# os21_smt.net
KiCad netlist of a schematic drawn in EAGLE
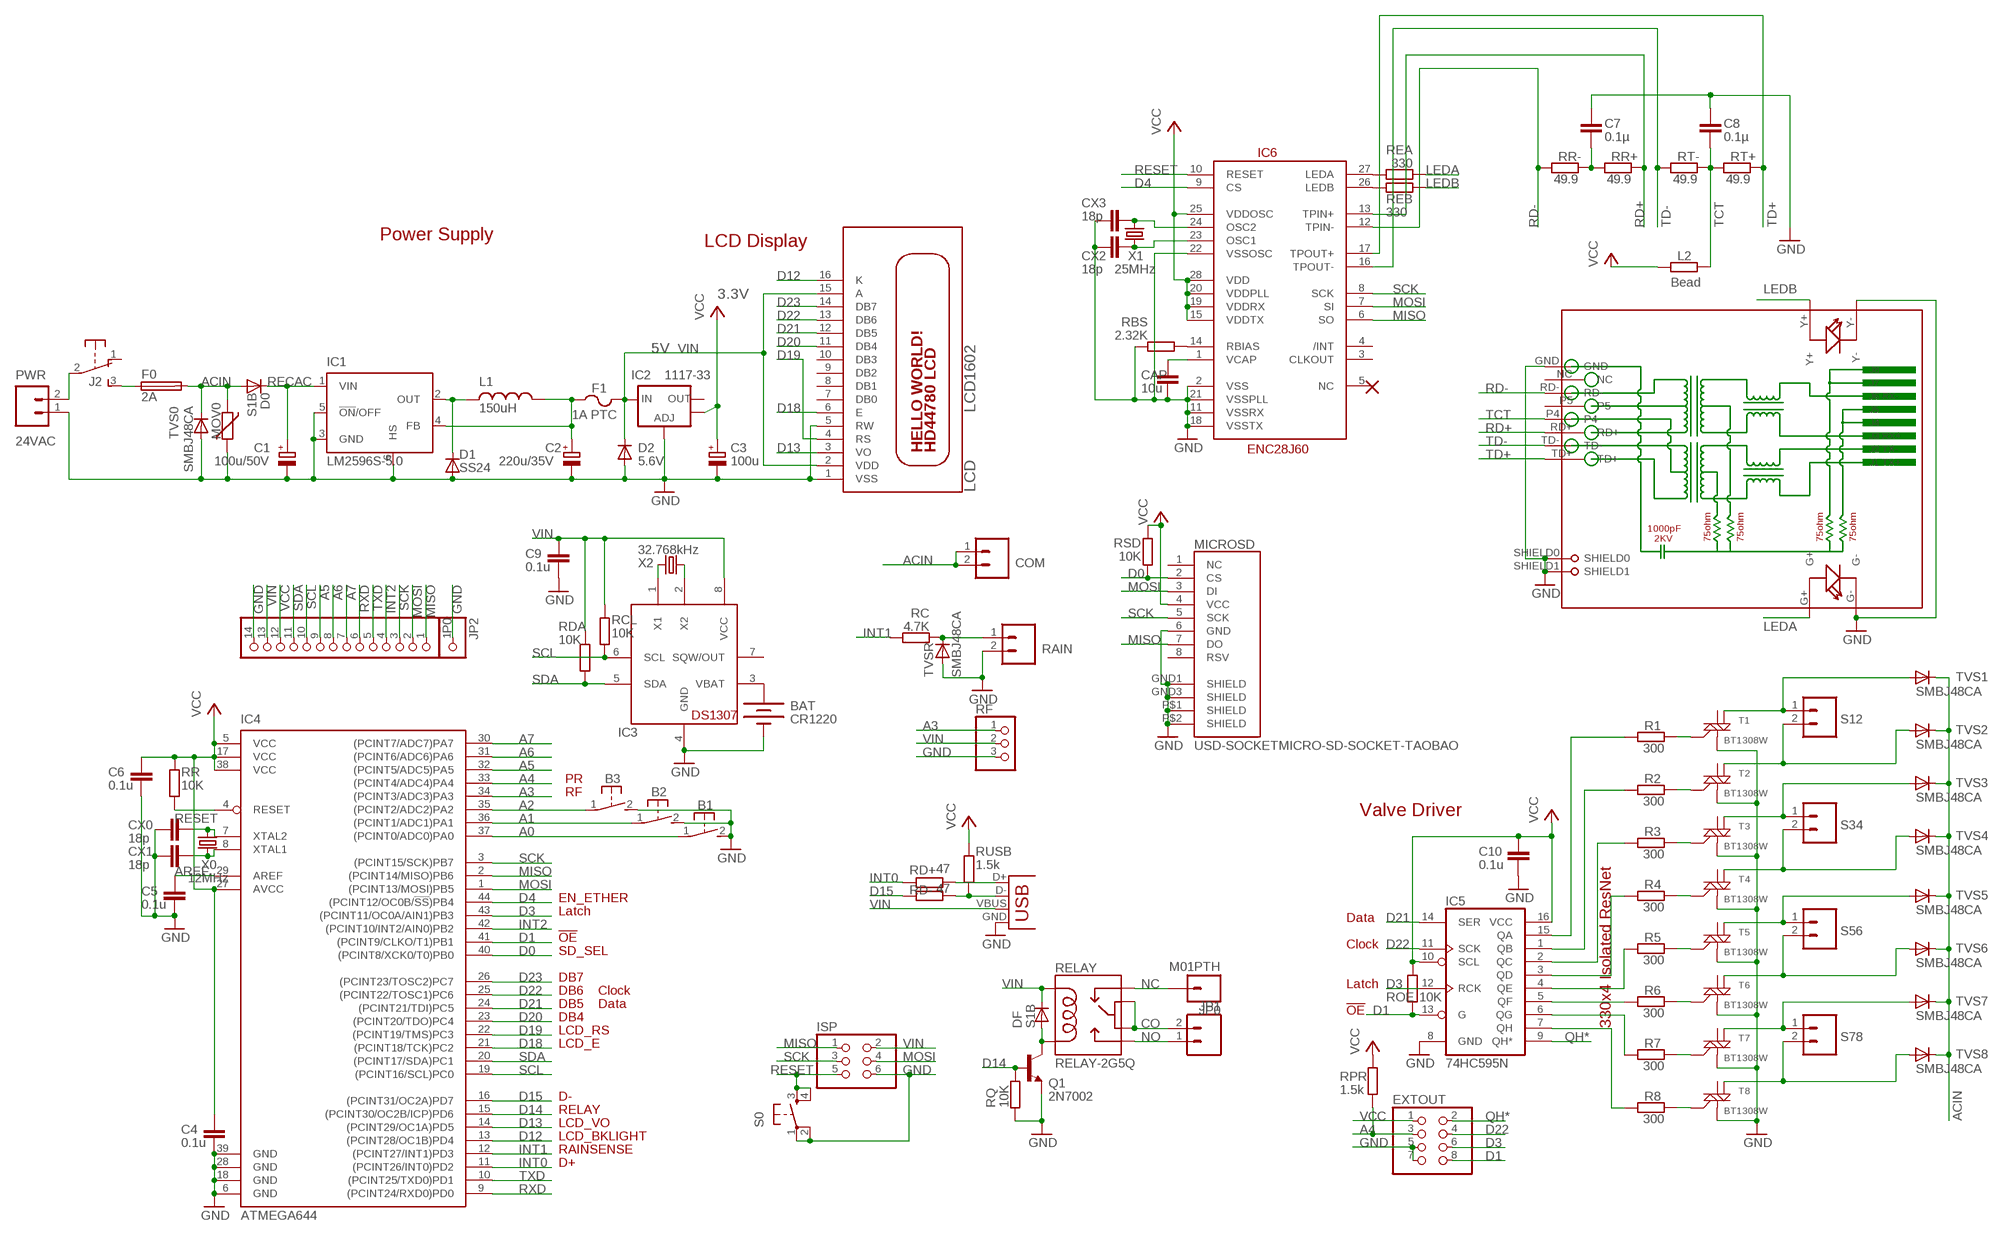
[diagram p0: schematic, sheet 1]

(export (version "E")
  (design (tool "Eeschema 10.0.6"))
  (components
    (comp (ref "B1")
      (value "31-XX")
      (footprint "eagle-import:B3F-31XX")
      (libsource (lib "eagle-import") (part "31-XX"))
    )
    (comp (ref "B2")
      (value "31-XX")
      (footprint "eagle-import:B3F-31XX")
      (libsource (lib "eagle-import") (part "31-XX"))
    )
    (comp (ref "B3")
      (value "31-XX")
      (footprint "eagle-import:B3F-31XX")
      (libsource (lib "eagle-import") (part "31-XX"))
    )
    (comp (ref "BAT")
      (value "CR1220")
      (footprint "eagle-import:BATTCON_12MM_SMT")
      (libsource (lib "eagle-import") (part "BATTERYBATTERY_12MM_SMT"))
    )
    (comp (ref "C1")
      (value "100u/50V")
      (footprint "eagle-import:E3,5-8")
      (libsource (lib "eagle-import") (part "CPOL-EUE3.5-8"))
    )
    (comp (ref "C2")
      (value "220u/35V")
      (footprint "eagle-import:E3,5-8")
      (libsource (lib "eagle-import") (part "CPOL-EUE3.5-8"))
    )
    (comp (ref "C3")
      (value "100u")
      (footprint "eagle-import:PANASONIC_D")
      (libsource (lib "eagle-import") (part "CPOL-EUD"))
    )
    (comp (ref "C4")
      (value "0.1u")
      (footprint "eagle-import:C0805")
      (libsource (lib "eagle-import") (part "C-EUC0805"))
    )
    (comp (ref "C5")
      (value "0.1u")
      (footprint "eagle-import:C0805")
      (libsource (lib "eagle-import") (part "C-EUC0805"))
    )
    (comp (ref "C6")
      (value "0.1u")
      (footprint "eagle-import:C0805")
      (libsource (lib "eagle-import") (part "C-EUC0805"))
    )
    (comp (ref "C7")
      (value "0.1µ")
      (footprint "eagle-import:C0805")
      (libsource (lib "eagle-import") (part "resistor_C-EUC0805"))
    )
    (comp (ref "C8")
      (value "0.1µ")
      (footprint "eagle-import:C0805")
      (libsource (lib "eagle-import") (part "resistor_C-EUC0805"))
    )
    (comp (ref "C9")
      (value "0.1u")
      (footprint "eagle-import:C0805")
      (libsource (lib "eagle-import") (part "C-EUC0805"))
    )
    (comp (ref "C10")
      (value "0.1u")
      (footprint "eagle-import:C0805")
      (libsource (lib "eagle-import") (part "C-EUC0805"))
    )
    (comp (ref "CAP")
      (value "10u")
      (footprint "eagle-import:C0805")
      (libsource (lib "eagle-import") (part "resistor_C-EUC0805"))
    )
    (comp (ref "COM")
      (value "M025MM-X")
      (footprint "eagle-import:SCREWTERMINAL-5MM-2-X")
      (libsource (lib "eagle-import") (part "M025MM-X"))
    )
    (comp (ref "CX0")
      (value "18p")
      (footprint "eagle-import:C0805")
      (libsource (lib "eagle-import") (part "resistor_C-EUC0805"))
    )
    (comp (ref "CX1")
      (value "18p")
      (footprint "eagle-import:C0805")
      (libsource (lib "eagle-import") (part "resistor_C-EUC0805"))
    )
    (comp (ref "CX2")
      (value "18p")
      (footprint "eagle-import:C0805")
      (libsource (lib "eagle-import") (part "resistor_C-EUC0805"))
    )
    (comp (ref "CX3")
      (value "18p")
      (footprint "eagle-import:C0805")
      (libsource (lib "eagle-import") (part "resistor_C-EUC0805"))
    )
    (comp (ref "D0")
      (value "S1B")
      (footprint "eagle-import:DO-214AC")
      (libsource (lib "eagle-import") (part "DIODE-DO-214AC"))
    )
    (comp (ref "D1")
      (value "SS24")
      (footprint "eagle-import:SMB")
      (libsource (lib "eagle-import") (part "DIODE-SMB"))
    )
    (comp (ref "D2")
      (value "5.6V")
      (footprint "eagle-import:MINIMELF")
      (libsource (lib "eagle-import") (part "DIODE-MINIMELF"))
    )
    (comp (ref "DF")
      (value "S1B")
      (footprint "eagle-import:DO-214AC")
      (libsource (lib "eagle-import") (part "DIODE-DO-214AC"))
    )
    (comp (ref "EXTOUT")
      (value "PINHD-2X4")
      (footprint "eagle-import:2X04")
      (libsource (lib "eagle-import") (part "PINHD-2X4"))
    )
    (comp (ref "F0")
      (value "2A")
      (footprint "eagle-import:SHK20L")
      (libsource (lib "eagle-import") (part "FUSESHK20L"))
    )
    (comp (ref "F1")
      (value "1A PTC")
      (footprint "eagle-import:1812")
      (libsource (lib "eagle-import") (part "PTCFUSE-1812"))
    )
    (comp (ref "IC1")
      (value "LM2596S-5.0")
      (footprint "eagle-import:TO263-5")
      (fields (field (name "MF") "NATIONAL SEMICONDUCTOR") (field (name "MPN") "LM2596S-ADJ/NOPB"))
      (libsource (lib "eagle-import") (part "LM2596S"))
    )
    (comp (ref "IC2")
      (value "1117-33")
      (footprint "eagle-import:SOT223")
      (libsource (lib "eagle-import") (part "V_REG_LM1117SOT223"))
    )
    (comp (ref "IC3")
      (value "DS1307")
      (footprint "eagle-import:SO08")
      (libsource (lib "eagle-import") (part "DS1307SOIC"))
    )
    (comp (ref "IC4")
      (value "ATMEGA644")
      (footprint "eagle-import:TQFP44")
      (fields (field (name "MPN") "ATMEGA644PV-10AU"))
      (libsource (lib "eagle-import") (part "ATMEGA644A"))
    )
    (comp (ref "IC5")
      (value "74HC595N")
      (footprint "eagle-import:SO16")
      (libsource (lib "eagle-import") (part "74595DLS"))
    )
    (comp (ref "IC6")
      (value "ENC28J60")
      (footprint "eagle-import:SOIC28WLONG")
      (libsource (lib "eagle-import") (part "ENC28J60SO28LONG"))
    )
    (comp (ref "ISP")
      (value "PINHD-2X3")
      (footprint "eagle-import:2X03")
      (libsource (lib "eagle-import") (part "PINHD-2X3"))
    )
    (comp (ref "J2")
      (value "EG1206")
      (footprint "eagle-import:EG1206")
      (libsource (lib "eagle-import") (part "EG1206"))
    )
    (comp (ref "JP0")
      (value "M01PTH")
      (footprint "eagle-import:1X01")
      (libsource (lib "eagle-import") (part "M01PTH"))
    )
    (comp (ref "JP1")
      (value "M025MM-X")
      (footprint "eagle-import:SCREWTERMINAL-5MM-2-X")
      (libsource (lib "eagle-import") (part "M025MM-X"))
    )
    (comp (ref "JP2")
      (value "PINHD-1X1CB")
      (footprint "eagle-import:1X01-CLEANBIG")
      (libsource (lib "eagle-import") (part "PINHD-1X1CB"))
    )
    (comp (ref "L1")
      (value "150uH")
      (footprint "eagle-import:CDRH125")
      (libsource (lib "eagle-import") (part "INDUCTORPWR"))
    )
    (comp (ref "L2")
      (value "Bead")
      (footprint "eagle-import:R0805")
      (libsource (lib "eagle-import") (part "R-EU_R0805"))
    )
    (comp (ref "LCD")
      (value "LCD1602")
      (footprint "eagle-import:LCD1602A")
      (libsource (lib "eagle-import") (part "HD44780LCDNOHOLE"))
    )
    (comp (ref "MICROSD")
      (value "USD-SOCKETMICRO-SD-SOCKET-TAOBAO")
      (footprint "eagle-import:MICRO-SD-SOCKET-TAOBAO")
      (libsource (lib "eagle-import") (part "USD-SOCKETMICRO-SD-SOCKET-TAOBAO"))
    )
    (comp (ref "MOV0")
      (value "MOV")
      (footprint "eagle-import:R-5")
      (libsource (lib "eagle-import") (part "VARISTOR-5"))
    )
    (comp (ref "P0")
      (value "PINHD-1X14-CB")
      (footprint "eagle-import:1X14-CB")
      (libsource (lib "eagle-import") (part "PINHD-1X14-CB"))
    )
    (comp (ref "PWR")
      (value "24VAC")
      (footprint "eagle-import:SCREWTERMINAL-4MM-2-X")
      (libsource (lib "eagle-import") (part "M024MM-X"))
    )
    (comp (ref "Q1")
      (value "2N7002")
      (footprint "eagle-import:SOT23-3")
      (libsource (lib "eagle-import") (part "TRANSISTOR_NPNSOT23-3"))
    )
    (comp (ref "R1")
      (value "300")
      (footprint "eagle-import:R0805")
      (libsource (lib "eagle-import") (part "R-EU_R0805"))
    )
    (comp (ref "R2")
      (value "300")
      (footprint "eagle-import:R0805")
      (libsource (lib "eagle-import") (part "R-EU_R0805"))
    )
    (comp (ref "R3")
      (value "300")
      (footprint "eagle-import:R0805")
      (libsource (lib "eagle-import") (part "R-EU_R0805"))
    )
    (comp (ref "R4")
      (value "300")
      (footprint "eagle-import:R0805")
      (libsource (lib "eagle-import") (part "R-EU_R0805"))
    )
    (comp (ref "R5")
      (value "300")
      (footprint "eagle-import:R0805")
      (libsource (lib "eagle-import") (part "R-EU_R0805"))
    )
    (comp (ref "R6")
      (value "300")
      (footprint "eagle-import:R0805")
      (libsource (lib "eagle-import") (part "R-EU_R0805"))
    )
    (comp (ref "R7")
      (value "300")
      (footprint "eagle-import:R0805")
      (libsource (lib "eagle-import") (part "R-EU_R0805"))
    )
    (comp (ref "R8")
      (value "300")
      (footprint "eagle-import:R0805")
      (libsource (lib "eagle-import") (part "R-EU_R0805"))
    )
    (comp (ref "RAIN")
      (value "M025MM-X")
      (footprint "eagle-import:SCREWTERMINAL-5MM-2-X")
      (libsource (lib "eagle-import") (part "M025MM-X"))
    )
    (comp (ref "RBS")
      (value "2.32K")
      (footprint "eagle-import:R0805")
      (libsource (lib "eagle-import") (part "R-EU_R0805"))
    )
    (comp (ref "RC")
      (value "4.7K")
      (footprint "eagle-import:R0805")
      (libsource (lib "eagle-import") (part "R-EU_R0805"))
    )
    (comp (ref "RCL")
      (value "10K")
      (footprint "eagle-import:R0805")
      (libsource (lib "eagle-import") (part "R-EU_R0805"))
    )
    (comp (ref "RD+")
      (value "47")
      (footprint "eagle-import:R0805")
      (libsource (lib "eagle-import") (part "R-EU_R0805"))
    )
    (comp (ref "RD-")
      (value "47")
      (footprint "eagle-import:R0805")
      (libsource (lib "eagle-import") (part "R-EU_R0805"))
    )
    (comp (ref "RDA")
      (value "10K")
      (footprint "eagle-import:R0805")
      (libsource (lib "eagle-import") (part "R-EU_R0805"))
    )
    (comp (ref "REA")
      (value "330")
      (footprint "eagle-import:R0805")
      (libsource (lib "eagle-import") (part "R-EU_R0805"))
    )
    (comp (ref "REB")
      (value "330")
      (footprint "eagle-import:R0805")
      (libsource (lib "eagle-import") (part "R-EU_R0805"))
    )
    (comp (ref "RELAY")
      (value "RELAY-2G5Q")
      (footprint "eagle-import:RELAY-G5V")
      (libsource (lib "eagle-import") (part "RELAY-2G5Q"))
    )
    (comp (ref "RF")
      (value "PINHD-1X3")
      (footprint "eagle-import:1X03")
      (libsource (lib "eagle-import") (part "PINHD-1X3"))
    )
    (comp (ref "RJ45")
      (value "HR911105A")
      (footprint "eagle-import:HR911105A")
      (libsource (lib "eagle-import") (part "HR911105A"))
    )
    (comp (ref "ROE")
      (value "10K")
      (footprint "eagle-import:R0805")
      (libsource (lib "eagle-import") (part "R-EU_R0805"))
    )
    (comp (ref "RPR")
      (value "1.5k")
      (footprint "eagle-import:R0805")
      (libsource (lib "eagle-import") (part "R-EU_R0805"))
    )
    (comp (ref "RQ")
      (value "10K")
      (footprint "eagle-import:R0805")
      (libsource (lib "eagle-import") (part "R-EU_R0805"))
    )
    (comp (ref "RR")
      (value "10K")
      (footprint "eagle-import:R0805")
      (libsource (lib "eagle-import") (part "R-EU_R0805"))
    )
    (comp (ref "RR+")
      (value "49.9")
      (footprint "eagle-import:R0805")
      (libsource (lib "eagle-import") (part "R-EU_R0805"))
    )
    (comp (ref "RR-")
      (value "49.9")
      (footprint "eagle-import:R0805")
      (libsource (lib "eagle-import") (part "R-EU_R0805"))
    )
    (comp (ref "RSD")
      (value "10K")
      (footprint "eagle-import:R0805")
      (libsource (lib "eagle-import") (part "R-EU_R0805"))
    )
    (comp (ref "RT+")
      (value "49.9")
      (footprint "eagle-import:R0805")
      (libsource (lib "eagle-import") (part "R-EU_R0805"))
    )
    (comp (ref "RT-")
      (value "49.9")
      (footprint "eagle-import:R0805")
      (libsource (lib "eagle-import") (part "R-EU_R0805"))
    )
    (comp (ref "RUSB")
      (value "1.5k")
      (footprint "eagle-import:R0805")
      (libsource (lib "eagle-import") (part "R-EU_R0805"))
    )
    (comp (ref "S0")
      (value "TAC_SWITCHSMD")
      (footprint "eagle-import:TACTILE_SWITCH_SMD")
      (libsource (lib "eagle-import") (part "TAC_SWITCHSMD"))
    )
    (comp (ref "S12")
      (value "M025MM-X")
      (footprint "eagle-import:SCREWTERMINAL-5MM-2-X")
      (libsource (lib "eagle-import") (part "M025MM-X"))
    )
    (comp (ref "S34")
      (value "M025MM-X")
      (footprint "eagle-import:SCREWTERMINAL-5MM-2-X")
      (libsource (lib "eagle-import") (part "M025MM-X"))
    )
    (comp (ref "S56")
      (value "M025MM-X")
      (footprint "eagle-import:SCREWTERMINAL-5MM-2-X")
      (libsource (lib "eagle-import") (part "M025MM-X"))
    )
    (comp (ref "S78")
      (value "M025MM-X")
      (footprint "eagle-import:SCREWTERMINAL-5MM-2-X")
      (libsource (lib "eagle-import") (part "M025MM-X"))
    )
    (comp (ref "T1")
      (value "BT1308W")
      (footprint "eagle-import:SOT223")
      (libsource (lib "eagle-import") (part "MAC97SOT223"))
    )
    (comp (ref "T2")
      (value "BT1308W")
      (footprint "eagle-import:SOT223")
      (libsource (lib "eagle-import") (part "MAC97SOT223"))
    )
    (comp (ref "T3")
      (value "BT1308W")
      (footprint "eagle-import:SOT223")
      (libsource (lib "eagle-import") (part "MAC97SOT223"))
    )
    (comp (ref "T4")
      (value "BT1308W")
      (footprint "eagle-import:SOT223")
      (libsource (lib "eagle-import") (part "MAC97SOT223"))
    )
    (comp (ref "T5")
      (value "BT1308W")
      (footprint "eagle-import:SOT223")
      (libsource (lib "eagle-import") (part "MAC97SOT223"))
    )
    (comp (ref "T6")
      (value "BT1308W")
      (footprint "eagle-import:SOT223")
      (libsource (lib "eagle-import") (part "MAC97SOT223"))
    )
    (comp (ref "T7")
      (value "BT1308W")
      (footprint "eagle-import:SOT223")
      (libsource (lib "eagle-import") (part "MAC97SOT223"))
    )
    (comp (ref "T8")
      (value "BT1308W")
      (footprint "eagle-import:SOT223")
      (libsource (lib "eagle-import") (part "MAC97SOT223"))
    )
    (comp (ref "TVS0")
      (value "SMBJ48CA")
      (footprint "eagle-import:SMB")
      (libsource (lib "eagle-import") (part "DIODE-SMB"))
    )
    (comp (ref "TVS1")
      (value "SMBJ48CA")
      (footprint "eagle-import:SMB")
      (libsource (lib "eagle-import") (part "DIODE-SMB"))
    )
    (comp (ref "TVS2")
      (value "SMBJ48CA")
      (footprint "eagle-import:SMB")
      (libsource (lib "eagle-import") (part "DIODE-SMB"))
    )
    (comp (ref "TVS3")
      (value "SMBJ48CA")
      (footprint "eagle-import:SMB")
      (libsource (lib "eagle-import") (part "DIODE-SMB"))
    )
    (comp (ref "TVS4")
      (value "SMBJ48CA")
      (footprint "eagle-import:SMB")
      (libsource (lib "eagle-import") (part "DIODE-SMB"))
    )
    (comp (ref "TVS5")
      (value "SMBJ48CA")
      (footprint "eagle-import:SMB")
      (libsource (lib "eagle-import") (part "DIODE-SMB"))
    )
    (comp (ref "TVS6")
      (value "SMBJ48CA")
      (footprint "eagle-import:SMB")
      (libsource (lib "eagle-import") (part "DIODE-SMB"))
    )
    (comp (ref "TVS7")
      (value "SMBJ48CA")
      (footprint "eagle-import:SMB")
      (libsource (lib "eagle-import") (part "DIODE-SMB"))
    )
    (comp (ref "TVS8")
      (value "SMBJ48CA")
      (footprint "eagle-import:SMB")
      (libsource (lib "eagle-import") (part "DIODE-SMB"))
    )
    (comp (ref "TVSR")
      (value "SMBJ48CA")
      (footprint "eagle-import:SMB")
      (libsource (lib "eagle-import") (part "DIODE-SMB"))
    )
    (comp (ref "USB")
      (value "USBPTH")
      (footprint "eagle-import:USB-B-PTH")
      (libsource (lib "eagle-import") (part "USBPTH"))
    )
    (comp (ref "X0")
      (value "12MHz")
      (footprint "eagle-import:HC49U-V")
      (libsource (lib "eagle-import") (part "CRYSTALHC49UV"))
    )
    (comp (ref "X1")
      (value "25MHz")
      (footprint "eagle-import:HC49U-V")
      (libsource (lib "eagle-import") (part "CRYSTALHC49UV"))
    )
    (comp (ref "X2")
      (value "32.768kHz")
      (footprint "eagle-import:TC38H")
      (libsource (lib "eagle-import") (part "crystal_CRYSTALTC38H"))
    )
  )
  (nets
    (net (code "1") (name "/A0") (class "Default")
      (node (ref "B1") (pin "1") (pinfunction "P_1") (pintype "passive"))
      (node (ref "IC4") (pin "37") (pinfunction "(PCINT0/ADC0)PA0_37") (pintype "bidirectional"))
    )
    (net (code "2") (name "/A1") (class "Default")
      (node (ref "B2") (pin "1") (pinfunction "P_1") (pintype "passive"))
      (node (ref "IC4") (pin "36") (pinfunction "(PCINT1/ADC1)PA1_36") (pintype "bidirectional"))
    )
    (net (code "3") (name "/A2") (class "Default")
      (node (ref "B3") (pin "1") (pinfunction "P_1") (pintype "passive"))
      (node (ref "IC4") (pin "35") (pinfunction "(PCINT2/ADC2)PA2_35") (pintype "bidirectional"))
    )
    (net (code "4") (name "/A3") (class "Default")
      (node (ref "IC4") (pin "34") (pinfunction "(PCINT3/ADC3)PA3_34") (pintype "bidirectional"))
      (node (ref "RF") (pin "1") (pinfunction "1_1") (pintype "passive"))
    )
    (net (code "5") (name "/A4") (class "Default")
      (node (ref "EXTOUT") (pin "3") (pinfunction "3_3") (pintype "passive"))
      (node (ref "IC4") (pin "33") (pinfunction "(PCINT4/ADC4)PA4_33") (pintype "bidirectional"))
      (node (ref "RPR") (pin "1") (pinfunction "1_1") (pintype "passive"))
    )
    (net (code "6") (name "/A5") (class "Default")
      (node (ref "IC4") (pin "32") (pinfunction "(PCINT5/ADC5)PA5_32") (pintype "bidirectional"))
      (node (ref "P0") (pin "9") (pinfunction "9_9") (pintype "passive"))
    )
    (net (code "7") (name "/A6") (class "Default")
      (node (ref "IC4") (pin "31") (pinfunction "(PCINT6/ADC6)PA6_31") (pintype "bidirectional"))
      (node (ref "P0") (pin "8") (pinfunction "8_8") (pintype "passive"))
    )
    (net (code "8") (name "/A7") (class "Default")
      (node (ref "IC4") (pin "30") (pinfunction "(PCINT7/ADC7)PA7_30") (pintype "bidirectional"))
      (node (ref "P0") (pin "7") (pinfunction "7_7") (pintype "passive"))
    )
    (net (code "9") (name "/ACIN") (class "Default")
      (node (ref "COM") (pin "1") (pinfunction "1_1") (pintype "passive"))
      (node (ref "COM") (pin "2") (pinfunction "2_2") (pintype "passive"))
      (node (ref "D0") (pin "A") (pinfunction "A_A") (pintype "passive"))
      (node (ref "F0") (pin "2A") (pinfunction "2_2A") (pintype "passive"))
      (node (ref "MOV0") (pin "1") (pinfunction "1_1") (pintype "passive"))
      (node (ref "TVS0") (pin "C") (pinfunction "C_C") (pintype "passive"))
      (node (ref "TVS1") (pin "C") (pinfunction "C_C") (pintype "passive"))
      (node (ref "TVS2") (pin "C") (pinfunction "C_C") (pintype "passive"))
      (node (ref "TVS3") (pin "C") (pinfunction "C_C") (pintype "passive"))
      (node (ref "TVS4") (pin "C") (pinfunction "C_C") (pintype "passive"))
      (node (ref "TVS5") (pin "C") (pinfunction "C_C") (pintype "passive"))
      (node (ref "TVS6") (pin "C") (pinfunction "C_C") (pintype "passive"))
      (node (ref "TVS7") (pin "C") (pinfunction "C_C") (pintype "passive"))
      (node (ref "TVS8") (pin "C") (pinfunction "C_C") (pintype "passive"))
    )
    (net (code "10") (name "/AREF") (class "Default")
      (node (ref "C5") (pin "1") (pinfunction "1_1") (pintype "passive"))
      (node (ref "IC4") (pin "29") (pinfunction "AREF_29") (pintype "passive"))
    )
    (net (code "11") (name "/CO") (class "Default")
      (node (ref "JP1") (pin "2") (pinfunction "2_2") (pintype "passive"))
      (node (ref "RELAY") (pin "5") (pinfunction "5_5") (pintype "bidirectional"))
      (node (ref "RELAY") (pin "6") (pinfunction "6_6") (pintype "bidirectional"))
    )
    (net (code "12") (name "/D0") (class "Default")
      (node (ref "IC4") (pin "40") (pinfunction "(PCINT8/XCK0/T0)PB0_40") (pintype "bidirectional"))
      (node (ref "MICROSD") (pin "2") (pinfunction "CS_2") (pintype "bidirectional"))
      (node (ref "RSD") (pin "1") (pinfunction "1_1") (pintype "passive"))
    )
    (net (code "13") (name "/D1") (class "Default")
      (node (ref "EXTOUT") (pin "8") (pinfunction "8_8") (pintype "passive"))
      (node (ref "IC4") (pin "41") (pinfunction "(PCINT9/CLKO/T1)PB1_41") (pintype "bidirectional"))
      (node (ref "IC5") (pin "13") (pinfunction "G_13") (pintype "input"))
      (node (ref "ROE") (pin "1") (pinfunction "1_1") (pintype "passive"))
    )
    (net (code "14") (name "/D3") (class "Default")
      (node (ref "EXTOUT") (pin "6") (pinfunction "6_6") (pintype "passive"))
      (node (ref "IC4") (pin "43") (pinfunction "(PCINT11/OC0A/AIN1)PB3_43") (pintype "bidirectional"))
      (node (ref "IC5") (pin "12") (pinfunction "RCK_12") (pintype "input"))
    )
    (net (code "15") (name "/D4") (class "Default")
      (node (ref "IC4") (pin "44") (pinfunction "(PCINT12/OC0B/~{SS})PB4_44") (pintype "bidirectional"))
      (node (ref "IC6") (pin "9") (pinfunction "CS_9") (pintype "bidirectional"))
    )
    (net (code "16") (name "/D12") (class "Default")
      (node (ref "IC4") (pin "13") (pinfunction "(PCINT28/OC1B)PD4_13") (pintype "bidirectional"))
      (node (ref "LCD") (pin "16") (pinfunction "K_16") (pintype "input"))
    )
    (net (code "17") (name "/D13") (class "Default")
      (node (ref "IC4") (pin "14") (pinfunction "(PCINT29/OC1A)PD5_14") (pintype "bidirectional"))
      (node (ref "LCD") (pin "3") (pinfunction "VO_3") (pintype "input"))
    )
    (net (code "18") (name "/D14") (class "Default")
      (node (ref "IC4") (pin "15") (pinfunction "(PCINT30/OC2B/ICP)PD6_15") (pintype "bidirectional"))
      (node (ref "Q1") (pin "1") (pinfunction "B_1") (pintype "passive"))
      (node (ref "RQ") (pin "1") (pinfunction "1_1") (pintype "passive"))
    )
    (net (code "19") (name "/D15") (class "Default")
      (node (ref "IC4") (pin "16") (pinfunction "(PCINT31/OC2A)PD7_16") (pintype "bidirectional"))
      (node (ref "RD-") (pin "1") (pinfunction "1_1") (pintype "passive"))
    )
    (net (code "20") (name "/D18") (class "Default")
      (node (ref "IC4") (pin "21") (pinfunction "(PCINT18/TCK)PC2_21") (pintype "output"))
      (node (ref "LCD") (pin "6") (pinfunction "E_6") (pintype "input"))
    )
    (net (code "21") (name "/D19") (class "Default")
      (node (ref "IC4") (pin "22") (pinfunction "(PCINT19/TMS)PC3_22") (pintype "output"))
      (node (ref "LCD") (pin "4") (pinfunction "RS_4") (pintype "input"))
    )
    (net (code "22") (name "/D20") (class "Default")
      (node (ref "IC4") (pin "23") (pinfunction "(PCINT20/TDO)PC4_23") (pintype "output"))
      (node (ref "LCD") (pin "11") (pinfunction "DB4_11") (pintype "bidirectional"))
    )
    (net (code "23") (name "/D21") (class "Default")
      (node (ref "IC4") (pin "24") (pinfunction "(PCINT21/TDI)PC5_24") (pintype "output"))
      (node (ref "IC5") (pin "14") (pinfunction "SER_14") (pintype "input"))
      (node (ref "LCD") (pin "12") (pinfunction "DB5_12") (pintype "bidirectional"))
    )
    (net (code "24") (name "/D22") (class "Default")
      (node (ref "EXTOUT") (pin "4") (pinfunction "4_4") (pintype "passive"))
      (node (ref "IC4") (pin "25") (pinfunction "(PCINT22/TOSC1)PC6_25") (pintype "output"))
      (node (ref "IC5") (pin "11") (pinfunction "SCK_11") (pintype "input"))
      (node (ref "LCD") (pin "13") (pinfunction "DB6_13") (pintype "bidirectional"))
    )
    (net (code "25") (name "/D23") (class "Default")
      (node (ref "IC4") (pin "26") (pinfunction "(PCINT23/TOSC2)PC7_26") (pintype "output"))
      (node (ref "LCD") (pin "14") (pinfunction "DB7_14") (pintype "bidirectional"))
    )
    (net (code "26") (name "/INT0") (class "Default")
      (node (ref "IC4") (pin "11") (pinfunction "(PCINT26/INT0)PD2_11") (pintype "bidirectional"))
      (node (ref "RD+") (pin "1") (pinfunction "1_1") (pintype "passive"))
    )
    (net (code "27") (name "/INT1") (class "Default")
      (node (ref "IC4") (pin "12") (pinfunction "(PCINT27/INT1)PD3_12") (pintype "bidirectional"))
      (node (ref "RC") (pin "1") (pinfunction "1_1") (pintype "passive"))
    )
    (net (code "28") (name "/INT2") (class "Default")
      (node (ref "IC4") (pin "42") (pinfunction "(PCINT10/INT2/AIN0)PB2_42") (pintype "bidirectional"))
      (node (ref "P0") (pin "4") (pinfunction "4_4") (pintype "passive"))
    )
    (net (code "29") (name "/LEDA") (class "Default")
      (node (ref "REA") (pin "2") (pinfunction "2_2") (pintype "passive"))
      (node (ref "RJ45") (pin "G+") (pinfunction "G+_G+") (pintype "bidirectional"))
    )
    (net (code "30") (name "/LEDB") (class "Default")
      (node (ref "REB") (pin "2") (pinfunction "2_2") (pintype "passive"))
      (node (ref "RJ45") (pin "Y+") (pinfunction "Y+_Y+") (pintype "bidirectional"))
    )
    (net (code "31") (name "/MISO") (class "Default")
      (node (ref "IC4") (pin "2") (pinfunction "(PCINT14/MISO)PB6_2") (pintype "bidirectional"))
      (node (ref "IC6") (pin "6") (pinfunction "SO_6") (pintype "bidirectional"))
      (node (ref "ISP") (pin "1") (pinfunction "1_1") (pintype "passive"))
      (node (ref "MICROSD") (pin "7") (pinfunction "DO_7") (pintype "bidirectional"))
      (node (ref "P0") (pin "1") (pinfunction "1_1") (pintype "passive"))
    )
    (net (code "32") (name "/MOSI") (class "Default")
      (node (ref "IC4") (pin "1") (pinfunction "(PCINT13/MOSI)PB5_1") (pintype "bidirectional"))
      (node (ref "IC6") (pin "7") (pinfunction "SI_7") (pintype "bidirectional"))
      (node (ref "ISP") (pin "4") (pinfunction "4_4") (pintype "passive"))
      (node (ref "MICROSD") (pin "3") (pinfunction "DI_3") (pintype "bidirectional"))
      (node (ref "P0") (pin "2") (pinfunction "2_2") (pintype "passive"))
    )
    (net (code "33") (name "/NC") (class "Default")
      (node (ref "JP0") (pin "1") (pinfunction "1_1") (pintype "passive"))
      (node (ref "RELAY") (pin "1") (pinfunction "1_1") (pintype "bidirectional"))
    )
    (net (code "34") (name "/NO") (class "Default")
      (node (ref "JP1") (pin "1") (pinfunction "1_1") (pintype "passive"))
      (node (ref "RELAY") (pin "10") (pinfunction "10_10") (pintype "bidirectional"))
    )
    (net (code "35") (name "/QH*") (class "Default")
      (node (ref "EXTOUT") (pin "2") (pinfunction "2_2") (pintype "passive"))
      (node (ref "IC5") (pin "9") (pinfunction "QH*_9") (pintype "tri_state"))
    )
    (net (code "36") (name "/RD+") (class "Default")
      (node (ref "IC6") (pin "13") (pinfunction "TPIN+_13") (pintype "bidirectional"))
      (node (ref "RJ45") (pin "RD+") (pinfunction "RD+_RD+") (pintype "bidirectional"))
      (node (ref "RR+") (pin "1") (pinfunction "1_1") (pintype "passive"))
    )
    (net (code "37") (name "/RD-") (class "Default")
      (node (ref "IC6") (pin "12") (pinfunction "TPIN-_12") (pintype "bidirectional"))
      (node (ref "RJ45") (pin "RD-") (pinfunction "RD-_RD-") (pintype "bidirectional"))
      (node (ref "RR-") (pin "2") (pinfunction "2_2") (pintype "passive"))
    )
    (net (code "38") (name "/RECAC") (class "Default")
      (node (ref "C1") (pin "+") (pinfunction "+_+") (pintype "passive"))
      (node (ref "D0") (pin "C") (pinfunction "C_C") (pintype "passive"))
      (node (ref "IC1") (pin "1") (pinfunction "VIN_1") (pintype "input"))
    )
    (net (code "39") (name "/RESET") (class "Default")
      (node (ref "IC4") (pin "4") (pinfunction "RESET_4") (pintype "input"))
      (node (ref "IC6") (pin "10") (pinfunction "RESET_10") (pintype "bidirectional"))
      (node (ref "ISP") (pin "5") (pinfunction "5_5") (pintype "passive"))
      (node (ref "RR") (pin "1") (pinfunction "1_1") (pintype "passive"))
      (node (ref "S0") (pin "3") (pinfunction "3_3") (pintype "passive"))
      (node (ref "S0") (pin "4") (pinfunction "4_4") (pintype "passive"))
    )
    (net (code "40") (name "/RXD") (class "Default")
      (node (ref "IC4") (pin "9") (pinfunction "(PCINT24/RXD0)PD0_9") (pintype "bidirectional"))
      (node (ref "P0") (pin "6") (pinfunction "6_6") (pintype "passive"))
    )
    (net (code "41") (name "/SCK") (class "Default")
      (node (ref "IC4") (pin "3") (pinfunction "(PCINT15/SCK)PB7_3") (pintype "bidirectional"))
      (node (ref "IC6") (pin "8") (pinfunction "SCK_8") (pintype "bidirectional"))
      (node (ref "ISP") (pin "3") (pinfunction "3_3") (pintype "passive"))
      (node (ref "MICROSD") (pin "5") (pinfunction "SCK_5") (pintype "bidirectional"))
      (node (ref "P0") (pin "3") (pinfunction "3_3") (pintype "passive"))
    )
    (net (code "42") (name "/SCL") (class "Default")
      (node (ref "IC3") (pin "6") (pinfunction "SCL_6") (pintype "bidirectional"))
      (node (ref "IC4") (pin "19") (pinfunction "(PCINT16/SCL)PC0_19") (pintype "output"))
      (node (ref "P0") (pin "10") (pinfunction "10_10") (pintype "passive"))
      (node (ref "RCL") (pin "1") (pinfunction "1_1") (pintype "passive"))
    )
    (net (code "43") (name "/SDA") (class "Default")
      (node (ref "IC3") (pin "5") (pinfunction "SDA_5") (pintype "bidirectional"))
      (node (ref "IC4") (pin "20") (pinfunction "(PCINT17/SDA)PC1_20") (pintype "output"))
      (node (ref "P0") (pin "11") (pinfunction "11_11") (pintype "passive"))
      (node (ref "RDA") (pin "1") (pinfunction "1_1") (pintype "passive"))
    )
    (net (code "44") (name "/TCT") (class "Default")
      (node (ref "C8") (pin "2") (pinfunction "2_2") (pintype "passive"))
      (node (ref "L2") (pin "1") (pinfunction "1_1") (pintype "passive"))
      (node (ref "RJ45") (pin "P4") (pinfunction "P4_P4") (pintype "bidirectional"))
      (node (ref "RT+") (pin "2") (pinfunction "2_2") (pintype "passive"))
      (node (ref "RT-") (pin "1") (pinfunction "1_1") (pintype "passive"))
    )
    (net (code "45") (name "/TD+") (class "Default")
      (node (ref "IC6") (pin "17") (pinfunction "TPOUT+_17") (pintype "bidirectional"))
      (node (ref "RJ45") (pin "TD+") (pinfunction "TD+_TD+") (pintype "bidirectional"))
      (node (ref "RT+") (pin "1") (pinfunction "1_1") (pintype "passive"))
    )
    (net (code "46") (name "/TD-") (class "Default")
      (node (ref "IC6") (pin "16") (pinfunction "TPOUT-_16") (pintype "bidirectional"))
      (node (ref "RJ45") (pin "TD-") (pinfunction "TD-_TD-") (pintype "bidirectional"))
      (node (ref "RT-") (pin "2") (pinfunction "2_2") (pintype "passive"))
    )
    (net (code "47") (name "/TXD") (class "Default")
      (node (ref "IC4") (pin "10") (pinfunction "(PCINT25/TXD0)PD1_10") (pintype "bidirectional"))
      (node (ref "P0") (pin "5") (pinfunction "5_5") (pintype "passive"))
    )
    (net (code "48") (name "/VIN") (class "Default")
      (node (ref "C9") (pin "1") (pinfunction "1_1") (pintype "passive"))
      (node (ref "D2") (pin "C") (pinfunction "C_C") (pintype "passive"))
      (node (ref "DF") (pin "C") (pinfunction "C_C") (pintype "passive"))
      (node (ref "F1") (pin "2") (pinfunction "2_2") (pintype "passive"))
      (node (ref "IC2") (pin "3") (pinfunction "IN_3") (pintype "input"))
      (node (ref "IC3") (pin "8") (pinfunction "VCC_8") (pintype "power_in"))
      (node (ref "ISP") (pin "2") (pinfunction "2_2") (pintype "passive"))
      (node (ref "LCD") (pin "15") (pinfunction "A_15") (pintype "input"))
      (node (ref "LCD") (pin "2") (pinfunction "VDD_2") (pintype "power_in"))
      (node (ref "P0") (pin "13") (pinfunction "13_13") (pintype "passive"))
      (node (ref "RCL") (pin "2") (pinfunction "2_2") (pintype "passive"))
      (node (ref "RDA") (pin "2") (pinfunction "2_2") (pintype "passive"))
      (node (ref "RELAY") (pin "2") (pinfunction "2_2") (pintype "bidirectional"))
      (node (ref "RF") (pin "2") (pinfunction "2_2") (pintype "passive"))
      (node (ref "USB") (pin "VBUS") (pinfunction "VBUS_VBUS") (pintype "bidirectional"))
    )
    (net (code "49") (name "GND") (class "Default")
      (node (ref "B1") (pin "2") (pinfunction "S_2") (pintype "passive"))
      (node (ref "B2") (pin "2") (pinfunction "S_2") (pintype "passive"))
      (node (ref "B3") (pin "2") (pinfunction "S_2") (pintype "passive"))
      (node (ref "BAT") (pin "P$1") (pinfunction "-_P$1") (pintype "power_in"))
      (node (ref "C1") (pin "-") (pinfunction "-_-") (pintype "passive"))
      (node (ref "C10") (pin "2") (pinfunction "2_2") (pintype "passive"))
      (node (ref "C2") (pin "-") (pinfunction "-_-") (pintype "passive"))
      (node (ref "C3") (pin "-") (pinfunction "-_-") (pintype "passive"))
      (node (ref "C4") (pin "2") (pinfunction "2_2") (pintype "passive"))
      (node (ref "C5") (pin "2") (pinfunction "2_2") (pintype "passive"))
      (node (ref "C6") (pin "2") (pinfunction "2_2") (pintype "passive"))
      (node (ref "C7") (pin "1") (pinfunction "1_1") (pintype "passive"))
      (node (ref "C8") (pin "1") (pinfunction "1_1") (pintype "passive"))
      (node (ref "C9") (pin "2") (pinfunction "2_2") (pintype "passive"))
      (node (ref "CAP") (pin "2") (pinfunction "2_2") (pintype "passive"))
      (node (ref "CX0") (pin "2") (pinfunction "2_2") (pintype "passive"))
      (node (ref "CX1") (pin "2") (pinfunction "2_2") (pintype "passive"))
      (node (ref "CX2") (pin "2") (pinfunction "2_2") (pintype "passive"))
      (node (ref "CX3") (pin "2") (pinfunction "2_2") (pintype "passive"))
      (node (ref "D1") (pin "A") (pinfunction "A_A") (pintype "passive"))
      (node (ref "D2") (pin "A") (pinfunction "A_A") (pintype "passive"))
      (node (ref "EXTOUT") (pin "5") (pinfunction "5_5") (pintype "passive"))
      (node (ref "EXTOUT") (pin "7") (pinfunction "7_7") (pintype "passive"))
      (node (ref "IC1") (pin "3") (pinfunction "GND_3") (pintype "power_in"))
      (node (ref "IC1") (pin "5") (pinfunction "~{ON}/OFF_5") (pintype "input"))
      (node (ref "IC1") (pin "6") (pinfunction "HS_6") (pintype "power_in"))
      (node (ref "IC2") (pin "1") (pinfunction "ADJ_1") (pintype "input"))
      (node (ref "IC3") (pin "4") (pinfunction "GND_4") (pintype "power_in"))
      (node (ref "IC4") (pin "18") (pinfunction "GND_18") (pintype "power_in"))
      (node (ref "IC4") (pin "28") (pinfunction "GND_28") (pintype "power_in"))
      (node (ref "IC4") (pin "39") (pinfunction "GND_39") (pintype "power_in"))
      (node (ref "IC4") (pin "6") (pinfunction "GND_6") (pintype "power_in"))
      (node (ref "IC5") (pin "8") (pinfunction "GND_8") (pintype "power_in"))
      (node (ref "IC6") (pin "11") (pinfunction "VSSRX_11") (pintype "bidirectional"))
      (node (ref "IC6") (pin "18") (pinfunction "VSSTX_18") (pintype "bidirectional"))
      (node (ref "IC6") (pin "2") (pinfunction "VSS_2") (pintype "bidirectional"))
      (node (ref "IC6") (pin "21") (pinfunction "VSSPLL_21") (pintype "bidirectional"))
      (node (ref "IC6") (pin "22") (pinfunction "VSSOSC_22") (pintype "bidirectional"))
      (node (ref "ISP") (pin "6") (pinfunction "6_6") (pintype "passive"))
      (node (ref "JP2") (pin "1") (pinfunction "1_1") (pintype "passive"))
      (node (ref "LCD") (pin "1") (pinfunction "VSS_1") (pintype "power_in"))
      (node (ref "LCD") (pin "5") (pinfunction "RW_5") (pintype "input"))
      (node (ref "MICROSD") (pin "6") (pinfunction "GND_6") (pintype "bidirectional"))
      (node (ref "MICROSD") (pin "GND1") (pinfunction "SHIELD_GND1") (pintype "bidirectional"))
      (node (ref "MICROSD") (pin "GND3") (pinfunction "SHIELD_GND3") (pintype "bidirectional"))
      (node (ref "MICROSD") (pin "P$1") (pinfunction "SHIELD_P$1") (pintype "bidirectional"))
      (node (ref "MICROSD") (pin "P$2") (pinfunction "SHIELD_P$2") (pintype "bidirectional"))
      (node (ref "MOV0") (pin "2") (pinfunction "2_2") (pintype "passive"))
      (node (ref "P0") (pin "14") (pinfunction "14_14") (pintype "passive"))
      (node (ref "PWR") (pin "1") (pinfunction "1_1") (pintype "passive"))
      (node (ref "Q1") (pin "2") (pinfunction "E_2") (pintype "passive"))
      (node (ref "RAIN") (pin "2") (pinfunction "2_2") (pintype "passive"))
      (node (ref "RBS") (pin "1") (pinfunction "1_1") (pintype "passive"))
      (node (ref "RF") (pin "3") (pinfunction "3_3") (pintype "passive"))
      (node (ref "RJ45") (pin "G-") (pinfunction "G-_G-") (pintype "bidirectional"))
      (node (ref "RJ45") (pin "GND") (pinfunction "GND_GND") (pintype "bidirectional"))
      (node (ref "RJ45") (pin "SHIELD0") (pinfunction "SHIELD0_SHIELD0") (pintype "bidirectional"))
      (node (ref "RJ45") (pin "SHIELD1") (pinfunction "SHIELD1_SHIELD1") (pintype "bidirectional"))
      (node (ref "RJ45") (pin "Y-") (pinfunction "Y-_Y-") (pintype "bidirectional"))
      (node (ref "RQ") (pin "2") (pinfunction "2_2") (pintype "passive"))
      (node (ref "S0") (pin "1") (pinfunction "1_1") (pintype "passive"))
      (node (ref "S0") (pin "2") (pinfunction "2_2") (pintype "passive"))
      (node (ref "T1") (pin "1") (pinfunction "M1_1") (pintype "bidirectional"))
      (node (ref "T2") (pin "1") (pinfunction "M1_1") (pintype "bidirectional"))
      (node (ref "T3") (pin "1") (pinfunction "M1_1") (pintype "bidirectional"))
      (node (ref "T4") (pin "1") (pinfunction "M1_1") (pintype "bidirectional"))
      (node (ref "T5") (pin "1") (pinfunction "M1_1") (pintype "bidirectional"))
      (node (ref "T6") (pin "1") (pinfunction "M1_1") (pintype "bidirectional"))
      (node (ref "T7") (pin "1") (pinfunction "M1_1") (pintype "bidirectional"))
      (node (ref "T8") (pin "1") (pinfunction "M1_1") (pintype "bidirectional"))
      (node (ref "TVS0") (pin "A") (pinfunction "A_A") (pintype "passive"))
      (node (ref "TVSR") (pin "A") (pinfunction "A_A") (pintype "passive"))
      (node (ref "USB") (pin "GND") (pinfunction "GND_GND") (pintype "bidirectional"))
    )
    (net (code "50") (name "Net-(BAT-+)") (class "Default")
      (node (ref "BAT") (pin "P$2") (pinfunction "+_P$2") (pintype "power_in"))
      (node (ref "IC3") (pin "3") (pinfunction "VBAT_3") (pintype "power_in"))
    )
    (net (code "51") (name "Net-(C7-Pad2)") (class "Default")
      (node (ref "C7") (pin "2") (pinfunction "2_2") (pintype "passive"))
      (node (ref "RR+") (pin "2") (pinfunction "2_2") (pintype "passive"))
      (node (ref "RR-") (pin "1") (pinfunction "1_1") (pintype "passive"))
    )
    (net (code "52") (name "Net-(F0-1)") (class "Default")
      (node (ref "F0") (pin "1A") (pinfunction "1_1A") (pintype "passive"))
      (node (ref "J2") (pin "3") (pinfunction "S_3") (pintype "passive"))
    )
    (net (code "53") (name "Net-(IC1-FB)") (class "Default")
      (node (ref "C2") (pin "+") (pinfunction "+_+") (pintype "passive"))
      (node (ref "F1") (pin "1") (pinfunction "1_1") (pintype "passive"))
      (node (ref "IC1") (pin "4") (pinfunction "FB_4") (pintype "input"))
      (node (ref "L1") (pin "2") (pinfunction "2_2") (pintype "passive"))
    )
    (net (code "54") (name "Net-(IC1-OUT)") (class "Default")
      (node (ref "D1") (pin "C") (pinfunction "C_C") (pintype "passive"))
      (node (ref "IC1") (pin "2") (pinfunction "OUT_2") (pintype "output"))
      (node (ref "L1") (pin "1") (pinfunction "1_1") (pintype "passive"))
    )
    (net (code "55") (name "Net-(IC3-X1)") (class "Default")
      (node (ref "IC3") (pin "1") (pinfunction "X1_1") (pintype "passive"))
      (node (ref "X2") (pin "2") (pinfunction "2_2") (pintype "passive"))
    )
    (net (code "56") (name "Net-(IC3-X2)") (class "Default")
      (node (ref "IC3") (pin "2") (pinfunction "X2_2") (pintype "passive"))
      (node (ref "X2") (pin "1") (pinfunction "1_1") (pintype "passive"))
    )
    (net (code "57") (name "Net-(IC4-XTAL1)") (class "Default")
      (node (ref "CX1") (pin "1") (pinfunction "1_1") (pintype "passive"))
      (node (ref "IC4") (pin "8") (pinfunction "XTAL1_8") (pintype "bidirectional"))
      (node (ref "X0") (pin "1") (pinfunction "1_1") (pintype "passive"))
    )
    (net (code "58") (name "Net-(IC4-XTAL2)") (class "Default")
      (node (ref "CX0") (pin "1") (pinfunction "1_1") (pintype "passive"))
      (node (ref "IC4") (pin "7") (pinfunction "XTAL2_7") (pintype "bidirectional"))
      (node (ref "X0") (pin "2") (pinfunction "2_2") (pintype "passive"))
    )
    (net (code "59") (name "Net-(IC5-QA)") (class "Default")
      (node (ref "IC5") (pin "15") (pinfunction "QA_15") (pintype "tri_state"))
      (node (ref "R1") (pin "2") (pinfunction "2_2") (pintype "passive"))
    )
    (net (code "60") (name "Net-(IC5-QB)") (class "Default")
      (node (ref "IC5") (pin "1") (pinfunction "QB_1") (pintype "tri_state"))
      (node (ref "R2") (pin "2") (pinfunction "2_2") (pintype "passive"))
    )
    (net (code "61") (name "Net-(IC5-QC)") (class "Default")
      (node (ref "IC5") (pin "2") (pinfunction "QC_2") (pintype "tri_state"))
      (node (ref "R3") (pin "2") (pinfunction "2_2") (pintype "passive"))
    )
    (net (code "62") (name "Net-(IC5-QD)") (class "Default")
      (node (ref "IC5") (pin "3") (pinfunction "QD_3") (pintype "tri_state"))
      (node (ref "R4") (pin "2") (pinfunction "2_2") (pintype "passive"))
    )
    (net (code "63") (name "Net-(IC5-QE)") (class "Default")
      (node (ref "IC5") (pin "4") (pinfunction "QE_4") (pintype "tri_state"))
      (node (ref "R5") (pin "2") (pinfunction "2_2") (pintype "passive"))
    )
    (net (code "64") (name "Net-(IC5-QF)") (class "Default")
      (node (ref "IC5") (pin "5") (pinfunction "QF_5") (pintype "tri_state"))
      (node (ref "R6") (pin "2") (pinfunction "2_2") (pintype "passive"))
    )
    (net (code "65") (name "Net-(IC5-QG)") (class "Default")
      (node (ref "IC5") (pin "6") (pinfunction "QG_6") (pintype "tri_state"))
      (node (ref "R7") (pin "2") (pinfunction "2_2") (pintype "passive"))
    )
    (net (code "66") (name "Net-(IC5-QH)") (class "Default")
      (node (ref "IC5") (pin "7") (pinfunction "QH_7") (pintype "tri_state"))
      (node (ref "R8") (pin "2") (pinfunction "2_2") (pintype "passive"))
    )
    (net (code "67") (name "Net-(IC6-LEDA)") (class "Default")
      (node (ref "IC6") (pin "27") (pinfunction "LEDA_27") (pintype "bidirectional"))
      (node (ref "REA") (pin "1") (pinfunction "1_1") (pintype "passive"))
    )
    (net (code "68") (name "Net-(IC6-LEDB)") (class "Default")
      (node (ref "IC6") (pin "26") (pinfunction "LEDB_26") (pintype "bidirectional"))
      (node (ref "REB") (pin "1") (pinfunction "1_1") (pintype "passive"))
    )
    (net (code "69") (name "Net-(IC6-OSC1)") (class "Default")
      (node (ref "CX2") (pin "1") (pinfunction "1_1") (pintype "passive"))
      (node (ref "IC6") (pin "23") (pinfunction "OSC1_23") (pintype "bidirectional"))
      (node (ref "X1") (pin "1") (pinfunction "1_1") (pintype "passive"))
    )
    (net (code "70") (name "Net-(IC6-OSC2)") (class "Default")
      (node (ref "CX3") (pin "1") (pinfunction "1_1") (pintype "passive"))
      (node (ref "IC6") (pin "24") (pinfunction "OSC2_24") (pintype "bidirectional"))
      (node (ref "X1") (pin "2") (pinfunction "2_2") (pintype "passive"))
    )
    (net (code "71") (name "Net-(IC6-RBIAS)") (class "Default")
      (node (ref "IC6") (pin "14") (pinfunction "RBIAS_14") (pintype "bidirectional"))
      (node (ref "RBS") (pin "2") (pinfunction "2_2") (pintype "passive"))
    )
    (net (code "72") (name "Net-(IC6-VCAP)") (class "Default")
      (node (ref "CAP") (pin "1") (pinfunction "1_1") (pintype "passive"))
      (node (ref "IC6") (pin "1") (pinfunction "VCAP_1") (pintype "bidirectional"))
    )
    (net (code "73") (name "Net-(J2-P)") (class "Default")
      (node (ref "J2") (pin "2") (pinfunction "P_2") (pintype "passive"))
      (node (ref "PWR") (pin "2") (pinfunction "2_2") (pintype "passive"))
    )
    (net (code "74") (name "Net-(Q1-C)") (class "Default")
      (node (ref "DF") (pin "A") (pinfunction "A_A") (pintype "passive"))
      (node (ref "Q1") (pin "3") (pinfunction "C_3") (pintype "passive"))
      (node (ref "RELAY") (pin "9") (pinfunction "9_9") (pintype "bidirectional"))
    )
    (net (code "75") (name "Net-(RAIN-Pad1)") (class "Default")
      (node (ref "RAIN") (pin "1") (pinfunction "1_1") (pintype "passive"))
      (node (ref "RC") (pin "2") (pinfunction "2_2") (pintype "passive"))
      (node (ref "TVSR") (pin "C") (pinfunction "C_C") (pintype "passive"))
    )
    (net (code "76") (name "Net-(RD+-Pad2)") (class "Default")
      (node (ref "RD+") (pin "2") (pinfunction "2_2") (pintype "passive"))
      (node (ref "USB") (pin "D+") (pinfunction "D+_D+") (pintype "bidirectional"))
    )
    (net (code "77") (name "Net-(RD--Pad2)") (class "Default")
      (node (ref "RD-") (pin "2") (pinfunction "2_2") (pintype "passive"))
      (node (ref "RUSB") (pin "1") (pinfunction "1_1") (pintype "passive"))
      (node (ref "USB") (pin "D-") (pinfunction "D-_D-") (pintype "bidirectional"))
    )
    (net (code "78") (name "Net-(T1-G)") (class "Default")
      (node (ref "R1") (pin "1") (pinfunction "1_1") (pintype "passive"))
      (node (ref "T1") (pin "3") (pinfunction "G_3") (pintype "bidirectional"))
    )
    (net (code "79") (name "Net-(T1-M2-4)") (class "Default")
      (node (ref "S12") (pin "1") (pinfunction "1_1") (pintype "passive"))
      (node (ref "T1") (pin "4") (pinfunction "M2-4_4") (pintype "bidirectional"))
      (node (ref "TVS1") (pin "A") (pinfunction "A_A") (pintype "passive"))
    )
    (net (code "80") (name "Net-(T2-G)") (class "Default")
      (node (ref "R2") (pin "1") (pinfunction "1_1") (pintype "passive"))
      (node (ref "T2") (pin "3") (pinfunction "G_3") (pintype "bidirectional"))
    )
    (net (code "81") (name "Net-(T2-M2-4)") (class "Default")
      (node (ref "S12") (pin "2") (pinfunction "2_2") (pintype "passive"))
      (node (ref "T2") (pin "4") (pinfunction "M2-4_4") (pintype "bidirectional"))
      (node (ref "TVS2") (pin "A") (pinfunction "A_A") (pintype "passive"))
    )
    (net (code "82") (name "Net-(T3-G)") (class "Default")
      (node (ref "R3") (pin "1") (pinfunction "1_1") (pintype "passive"))
      (node (ref "T3") (pin "3") (pinfunction "G_3") (pintype "bidirectional"))
    )
    (net (code "83") (name "Net-(T3-M2-4)") (class "Default")
      (node (ref "S34") (pin "1") (pinfunction "1_1") (pintype "passive"))
      (node (ref "T3") (pin "4") (pinfunction "M2-4_4") (pintype "bidirectional"))
      (node (ref "TVS3") (pin "A") (pinfunction "A_A") (pintype "passive"))
    )
    (net (code "84") (name "Net-(T4-G)") (class "Default")
      (node (ref "R4") (pin "1") (pinfunction "1_1") (pintype "passive"))
      (node (ref "T4") (pin "3") (pinfunction "G_3") (pintype "bidirectional"))
    )
    (net (code "85") (name "Net-(T4-M2-4)") (class "Default")
      (node (ref "S34") (pin "2") (pinfunction "2_2") (pintype "passive"))
      (node (ref "T4") (pin "4") (pinfunction "M2-4_4") (pintype "bidirectional"))
      (node (ref "TVS4") (pin "A") (pinfunction "A_A") (pintype "passive"))
    )
    (net (code "86") (name "Net-(T5-G)") (class "Default")
      (node (ref "R5") (pin "1") (pinfunction "1_1") (pintype "passive"))
      (node (ref "T5") (pin "3") (pinfunction "G_3") (pintype "bidirectional"))
    )
    (net (code "87") (name "Net-(T5-M2-4)") (class "Default")
      (node (ref "S56") (pin "1") (pinfunction "1_1") (pintype "passive"))
      (node (ref "T5") (pin "4") (pinfunction "M2-4_4") (pintype "bidirectional"))
      (node (ref "TVS5") (pin "A") (pinfunction "A_A") (pintype "passive"))
    )
    (net (code "88") (name "Net-(T6-G)") (class "Default")
      (node (ref "R6") (pin "1") (pinfunction "1_1") (pintype "passive"))
      (node (ref "T6") (pin "3") (pinfunction "G_3") (pintype "bidirectional"))
    )
    (net (code "89") (name "Net-(T6-M2-4)") (class "Default")
      (node (ref "S56") (pin "2") (pinfunction "2_2") (pintype "passive"))
      (node (ref "T6") (pin "4") (pinfunction "M2-4_4") (pintype "bidirectional"))
      (node (ref "TVS6") (pin "A") (pinfunction "A_A") (pintype "passive"))
    )
    (net (code "90") (name "Net-(T7-G)") (class "Default")
      (node (ref "R7") (pin "1") (pinfunction "1_1") (pintype "passive"))
      (node (ref "T7") (pin "3") (pinfunction "G_3") (pintype "bidirectional"))
    )
    (net (code "91") (name "Net-(T7-M2-4)") (class "Default")
      (node (ref "S78") (pin "1") (pinfunction "1_1") (pintype "passive"))
      (node (ref "T7") (pin "4") (pinfunction "M2-4_4") (pintype "bidirectional"))
      (node (ref "TVS7") (pin "A") (pinfunction "A_A") (pintype "passive"))
    )
    (net (code "92") (name "Net-(T8-G)") (class "Default")
      (node (ref "R8") (pin "1") (pinfunction "1_1") (pintype "passive"))
      (node (ref "T8") (pin "3") (pinfunction "G_3") (pintype "bidirectional"))
    )
    (net (code "93") (name "Net-(T8-M2-4)") (class "Default")
      (node (ref "S78") (pin "2") (pinfunction "2_2") (pintype "passive"))
      (node (ref "T8") (pin "4") (pinfunction "M2-4_4") (pintype "bidirectional"))
      (node (ref "TVS8") (pin "A") (pinfunction "A_A") (pintype "passive"))
    )
    (net (code "94") (name "VCC") (class "Default")
      (node (ref "C10") (pin "1") (pinfunction "1_1") (pintype "passive"))
      (node (ref "C3") (pin "+") (pinfunction "+_+") (pintype "passive"))
      (node (ref "C4") (pin "1") (pinfunction "1_1") (pintype "passive"))
      (node (ref "C6") (pin "1") (pinfunction "1_1") (pintype "passive"))
      (node (ref "EXTOUT") (pin "1") (pinfunction "1_1") (pintype "passive"))
      (node (ref "IC2") (pin "4") (pinfunction "OUT_4") (pintype "bidirectional"))
      (node (ref "IC4") (pin "17") (pinfunction "VCC_17") (pintype "power_in"))
      (node (ref "IC4") (pin "27") (pinfunction "AVCC_27") (pintype "power_in"))
      (node (ref "IC4") (pin "38") (pinfunction "VCC_38") (pintype "power_in"))
      (node (ref "IC4") (pin "5") (pinfunction "VCC_5") (pintype "power_in"))
      (node (ref "IC5") (pin "10") (pinfunction "SCL_10") (pintype "input"))
      (node (ref "IC5") (pin "16") (pinfunction "VCC_16") (pintype "power_in"))
      (node (ref "IC6") (pin "15") (pinfunction "VDDTX_15") (pintype "bidirectional"))
      (node (ref "IC6") (pin "19") (pinfunction "VDDRX_19") (pintype "bidirectional"))
      (node (ref "IC6") (pin "20") (pinfunction "VDDPLL_20") (pintype "bidirectional"))
      (node (ref "IC6") (pin "25") (pinfunction "VDDOSC_25") (pintype "bidirectional"))
      (node (ref "IC6") (pin "28") (pinfunction "VDD_28") (pintype "bidirectional"))
      (node (ref "L2") (pin "2") (pinfunction "2_2") (pintype "passive"))
      (node (ref "MICROSD") (pin "4") (pinfunction "VCC_4") (pintype "bidirectional"))
      (node (ref "P0") (pin "12") (pinfunction "12_12") (pintype "passive"))
      (node (ref "ROE") (pin "2") (pinfunction "2_2") (pintype "passive"))
      (node (ref "RPR") (pin "2") (pinfunction "2_2") (pintype "passive"))
      (node (ref "RR") (pin "2") (pinfunction "2_2") (pintype "passive"))
      (node (ref "RSD") (pin "2") (pinfunction "2_2") (pintype "passive"))
      (node (ref "RUSB") (pin "2") (pinfunction "2_2") (pintype "passive"))
    )
    (net (code "95") (name "unconnected-(IC2-OUT-Pad2)") (class "Default")
      (node (ref "IC2") (pin "2") (pinfunction "OUT_2") (pintype "bidirectional"))
    )
    (net (code "96") (name "unconnected-(IC3-SQW{slash}OUT-Pad7)") (class "Default")
      (node (ref "IC3") (pin "7") (pinfunction "SQW/OUT_7") (pintype "bidirectional"))
    )
    (net (code "97") (name "unconnected-(IC6-CLKOUT-Pad3)") (class "Default")
      (node (ref "IC6") (pin "3") (pinfunction "CLKOUT_3") (pintype "bidirectional"))
    )
    (net (code "98") (name "unconnected-(IC6-NC-Pad5)") (class "Default")
      (node (ref "IC6") (pin "5") (pinfunction "NC_5") (pintype "bidirectional"))
    )
    (net (code "99") (name "unconnected-(IC6-{slash}INT-Pad4)") (class "Default")
      (node (ref "IC6") (pin "4") (pinfunction "/INT_4") (pintype "bidirectional"))
    )
    (net (code "100") (name "unconnected-(J2-O-Pad1)") (class "Default")
      (node (ref "J2") (pin "1") (pinfunction "O_1") (pintype "passive"))
    )
    (net (code "101") (name "unconnected-(LCD-DB0-Pad7)") (class "Default")
      (node (ref "LCD") (pin "7") (pinfunction "DB0_7") (pintype "bidirectional"))
    )
    (net (code "102") (name "unconnected-(LCD-DB1-Pad8)") (class "Default")
      (node (ref "LCD") (pin "8") (pinfunction "DB1_8") (pintype "bidirectional"))
    )
    (net (code "103") (name "unconnected-(LCD-DB2-Pad9)") (class "Default")
      (node (ref "LCD") (pin "9") (pinfunction "DB2_9") (pintype "bidirectional"))
    )
    (net (code "104") (name "unconnected-(LCD-DB3-Pad10)") (class "Default")
      (node (ref "LCD") (pin "10") (pinfunction "DB3_10") (pintype "bidirectional"))
    )
    (net (code "105") (name "unconnected-(MICROSD-NC-Pad1)") (class "Default")
      (node (ref "MICROSD") (pin "1") (pinfunction "NC_1") (pintype "bidirectional"))
    )
    (net (code "106") (name "unconnected-(MICROSD-RSV-Pad8)") (class "Default")
      (node (ref "MICROSD") (pin "8") (pinfunction "RSV_8") (pintype "bidirectional"))
    )
    (net (code "107") (name "unconnected-(RJ45-PadNC)") (class "Default")
      (node (ref "RJ45") (pin "NC") (pinfunction "NC_NC") (pintype "bidirectional"))
    )
    (net (code "108") (name "unconnected-(RJ45-PadP5)") (class "Default")
      (node (ref "RJ45") (pin "P5") (pinfunction "P5_P5") (pintype "bidirectional"))
    )
    (net (code "109") (name "unconnected-(T1-M2-Pad2)") (class "Default")
      (node (ref "T1") (pin "2") (pinfunction "M2_2") (pintype "bidirectional"))
    )
    (net (code "110") (name "unconnected-(T2-M2-Pad2)") (class "Default")
      (node (ref "T2") (pin "2") (pinfunction "M2_2") (pintype "bidirectional"))
    )
    (net (code "111") (name "unconnected-(T3-M2-Pad2)") (class "Default")
      (node (ref "T3") (pin "2") (pinfunction "M2_2") (pintype "bidirectional"))
    )
    (net (code "112") (name "unconnected-(T4-M2-Pad2)") (class "Default")
      (node (ref "T4") (pin "2") (pinfunction "M2_2") (pintype "bidirectional"))
    )
    (net (code "113") (name "unconnected-(T5-M2-Pad2)") (class "Default")
      (node (ref "T5") (pin "2") (pinfunction "M2_2") (pintype "bidirectional"))
    )
    (net (code "114") (name "unconnected-(T6-M2-Pad2)") (class "Default")
      (node (ref "T6") (pin "2") (pinfunction "M2_2") (pintype "bidirectional"))
    )
    (net (code "115") (name "unconnected-(T7-M2-Pad2)") (class "Default")
      (node (ref "T7") (pin "2") (pinfunction "M2_2") (pintype "bidirectional"))
    )
    (net (code "116") (name "unconnected-(T8-M2-Pad2)") (class "Default")
      (node (ref "T8") (pin "2") (pinfunction "M2_2") (pintype "bidirectional"))
    )
  )
)
